# frontend.net
KiCad netlist of a schematic drawn in EAGLE
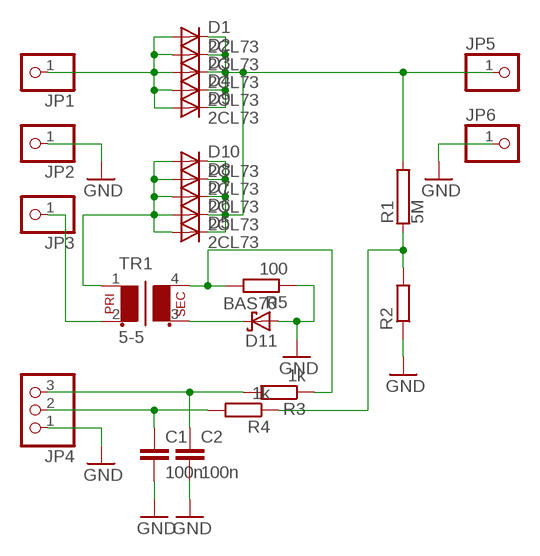
[diagram p0: schematic, sheet 1]

(export (version "E")
  (design (tool "Eeschema 10.0.6"))
  (components
    (comp (ref "C1")
      (value "100n")
      (footprint "eagle-import:C1206")
      (libsource (lib "eagle-import") (part "C-EUC1206"))
    )
    (comp (ref "C2")
      (value "100n")
      (footprint "eagle-import:C1206")
      (libsource (lib "eagle-import") (part "C-EUC1206"))
    )
    (comp (ref "D1")
      (value "2CL73")
      (footprint "eagle-import:DIODE-3-20")
      (libsource (lib "eagle-import") (part "2CL73"))
    )
    (comp (ref "D2")
      (value "2CL73")
      (footprint "eagle-import:DIODE-3-20")
      (libsource (lib "eagle-import") (part "2CL73"))
    )
    (comp (ref "D3")
      (value "2CL73")
      (footprint "eagle-import:DIODE-3-20")
      (libsource (lib "eagle-import") (part "2CL73"))
    )
    (comp (ref "D4")
      (value "2CL73")
      (footprint "eagle-import:DIODE-3-20")
      (libsource (lib "eagle-import") (part "2CL73"))
    )
    (comp (ref "D5")
      (value "2CL73")
      (footprint "eagle-import:DIODE-3-20")
      (libsource (lib "eagle-import") (part "2CL73"))
    )
    (comp (ref "D6")
      (value "2CL73")
      (footprint "eagle-import:DIODE-3-20")
      (libsource (lib "eagle-import") (part "2CL73"))
    )
    (comp (ref "D7")
      (value "2CL73")
      (footprint "eagle-import:DIODE-3-20")
      (libsource (lib "eagle-import") (part "2CL73"))
    )
    (comp (ref "D8")
      (value "2CL73")
      (footprint "eagle-import:DIODE-3-20")
      (libsource (lib "eagle-import") (part "2CL73"))
    )
    (comp (ref "D9")
      (value "2CL73")
      (footprint "eagle-import:DIODE-3-20")
      (libsource (lib "eagle-import") (part "2CL73"))
    )
    (comp (ref "D10")
      (value "2CL73")
      (footprint "eagle-import:DIODE-3-20")
      (libsource (lib "eagle-import") (part "2CL73"))
    )
    (comp (ref "D11")
      (value "BAS70")
      (footprint "eagle-import:SOT23")
      (libsource (lib "eagle-import") (part "BAS70"))
    )
    (comp (ref "JP1")
      (value "PINHD-1X1")
      (footprint "eagle-import:1X01")
      (libsource (lib "eagle-import") (part "PINHD-1X1"))
    )
    (comp (ref "JP2")
      (value "PINHD-1X1")
      (footprint "eagle-import:1X01")
      (libsource (lib "eagle-import") (part "PINHD-1X1"))
    )
    (comp (ref "JP3")
      (value "PINHD-1X1")
      (footprint "eagle-import:1X01")
      (libsource (lib "eagle-import") (part "PINHD-1X1"))
    )
    (comp (ref "JP4")
      (value "PINHD-1X3/90")
      (footprint "eagle-import:1X03_90")
      (libsource (lib "eagle-import") (part "PINHD-1X3/90"))
    )
    (comp (ref "JP5")
      (value "PINHD-1X1")
      (footprint "eagle-import:1X01")
      (libsource (lib "eagle-import") (part "PINHD-1X1"))
    )
    (comp (ref "JP6")
      (value "PINHD-1X1")
      (footprint "eagle-import:1X01")
      (libsource (lib "eagle-import") (part "PINHD-1X1"))
    )
    (comp (ref "R1")
      (value "5M")
      (footprint "eagle-import:CA4150")
      (libsource (lib "eagle-import") (part "RCA4150"))
    )
    (comp (ref "R2")
      (value "R-EU_R0805")
      (footprint "eagle-import:R0805")
      (libsource (lib "eagle-import") (part "R-EU_R0805"))
    )
    (comp (ref "R3")
      (value "1k")
      (footprint "eagle-import:R0805")
      (libsource (lib "eagle-import") (part "R-EU_R0805"))
    )
    (comp (ref "R4")
      (value "1k")
      (footprint "eagle-import:R0805")
      (libsource (lib "eagle-import") (part "R-EU_R0805"))
    )
    (comp (ref "R5")
      (value "100")
      (footprint "eagle-import:R0805")
      (libsource (lib "eagle-import") (part "R-EU_R0805"))
    )
    (comp (ref "TR1")
      (value "5-5")
      (footprint "eagle-import:RM4-4")
      (libsource (lib "eagle-import") (part "5-5"))
    )
  )
  (nets
    (net (code "1") (name "GND") (class "Default")
      (node (ref "C1") (pin "2") (pinfunction "2_2") (pintype "passive"))
      (node (ref "C2") (pin "2") (pinfunction "2_2") (pintype "passive"))
      (node (ref "D11") (pin "1") (pinfunction "A_1") (pintype "passive"))
      (node (ref "JP2") (pin "1") (pinfunction "1_1") (pintype "passive"))
      (node (ref "JP4") (pin "1") (pinfunction "1_1") (pintype "passive"))
      (node (ref "JP6") (pin "1") (pinfunction "1_1") (pintype "passive"))
      (node (ref "R2") (pin "1") (pinfunction "1_1") (pintype "passive"))
      (node (ref "R5") (pin "1") (pinfunction "1_1") (pintype "passive"))
    )
    (net (code "2") (name "Net-(C1-Pad1)") (class "Default")
      (node (ref "C1") (pin "1") (pinfunction "1_1") (pintype "passive"))
      (node (ref "JP4") (pin "2") (pinfunction "2_2") (pintype "passive"))
      (node (ref "R4") (pin "2") (pinfunction "2_2") (pintype "passive"))
    )
    (net (code "3") (name "Net-(C2-Pad1)") (class "Default")
      (node (ref "C2") (pin "1") (pinfunction "1_1") (pintype "passive"))
      (node (ref "JP4") (pin "3") (pinfunction "3_3") (pintype "passive"))
      (node (ref "R3") (pin "2") (pinfunction "2_2") (pintype "passive"))
    )
    (net (code "4") (name "Net-(D1-PadA)") (class "Default")
      (node (ref "D1") (pin "A") (pinfunction "A_A") (pintype "passive"))
      (node (ref "D2") (pin "A") (pinfunction "A_A") (pintype "passive"))
      (node (ref "D3") (pin "A") (pinfunction "A_A") (pintype "passive"))
      (node (ref "D4") (pin "A") (pinfunction "A_A") (pintype "passive"))
      (node (ref "D9") (pin "A") (pinfunction "A_A") (pintype "passive"))
      (node (ref "JP1") (pin "1") (pinfunction "1_1") (pintype "passive"))
    )
    (net (code "5") (name "Net-(D1-PadC)") (class "Default")
      (node (ref "D1") (pin "C") (pinfunction "C_C") (pintype "passive"))
      (node (ref "D10") (pin "C") (pinfunction "C_C") (pintype "passive"))
      (node (ref "D2") (pin "C") (pinfunction "C_C") (pintype "passive"))
      (node (ref "D3") (pin "C") (pinfunction "C_C") (pintype "passive"))
      (node (ref "D4") (pin "C") (pinfunction "C_C") (pintype "passive"))
      (node (ref "D5") (pin "C") (pinfunction "C_C") (pintype "passive"))
      (node (ref "D6") (pin "C") (pinfunction "C_C") (pintype "passive"))
      (node (ref "D7") (pin "C") (pinfunction "C_C") (pintype "passive"))
      (node (ref "D8") (pin "C") (pinfunction "C_C") (pintype "passive"))
      (node (ref "D9") (pin "C") (pinfunction "C_C") (pintype "passive"))
      (node (ref "JP5") (pin "1") (pinfunction "1_1") (pintype "passive"))
      (node (ref "R1") (pin "2") (pinfunction "2_2") (pintype "passive"))
    )
    (net (code "6") (name "Net-(D10-PadA)") (class "Default")
      (node (ref "D10") (pin "A") (pinfunction "A_A") (pintype "passive"))
      (node (ref "D5") (pin "A") (pinfunction "A_A") (pintype "passive"))
      (node (ref "D6") (pin "A") (pinfunction "A_A") (pintype "passive"))
      (node (ref "D7") (pin "A") (pinfunction "A_A") (pintype "passive"))
      (node (ref "D8") (pin "A") (pinfunction "A_A") (pintype "passive"))
      (node (ref "TR1") (pin "1") (pinfunction "1_1") (pintype "passive"))
    )
    (net (code "7") (name "Net-(D11-C)") (class "Default")
      (node (ref "D11") (pin "3") (pinfunction "C_3") (pintype "passive"))
      (node (ref "TR1") (pin "3") (pinfunction "3_3") (pintype "passive"))
    )
    (net (code "8") (name "Net-(JP3-Pad1)") (class "Default")
      (node (ref "JP3") (pin "1") (pinfunction "1_1") (pintype "passive"))
      (node (ref "TR1") (pin "2") (pinfunction "2_2") (pintype "passive"))
    )
    (net (code "9") (name "Net-(R1-Pad1)") (class "Default")
      (node (ref "R1") (pin "1") (pinfunction "1_1") (pintype "passive"))
      (node (ref "R2") (pin "2") (pinfunction "2_2") (pintype "passive"))
      (node (ref "R4") (pin "1") (pinfunction "1_1") (pintype "passive"))
    )
    (net (code "10") (name "Net-(R3-Pad1)") (class "Default")
      (node (ref "R3") (pin "1") (pinfunction "1_1") (pintype "passive"))
      (node (ref "R5") (pin "2") (pinfunction "2_2") (pintype "passive"))
      (node (ref "TR1") (pin "4") (pinfunction "4_4") (pintype "passive"))
    )
  )
)
